# MCU_Power.net
KiCad netlist of a schematic drawn in Altium Designer
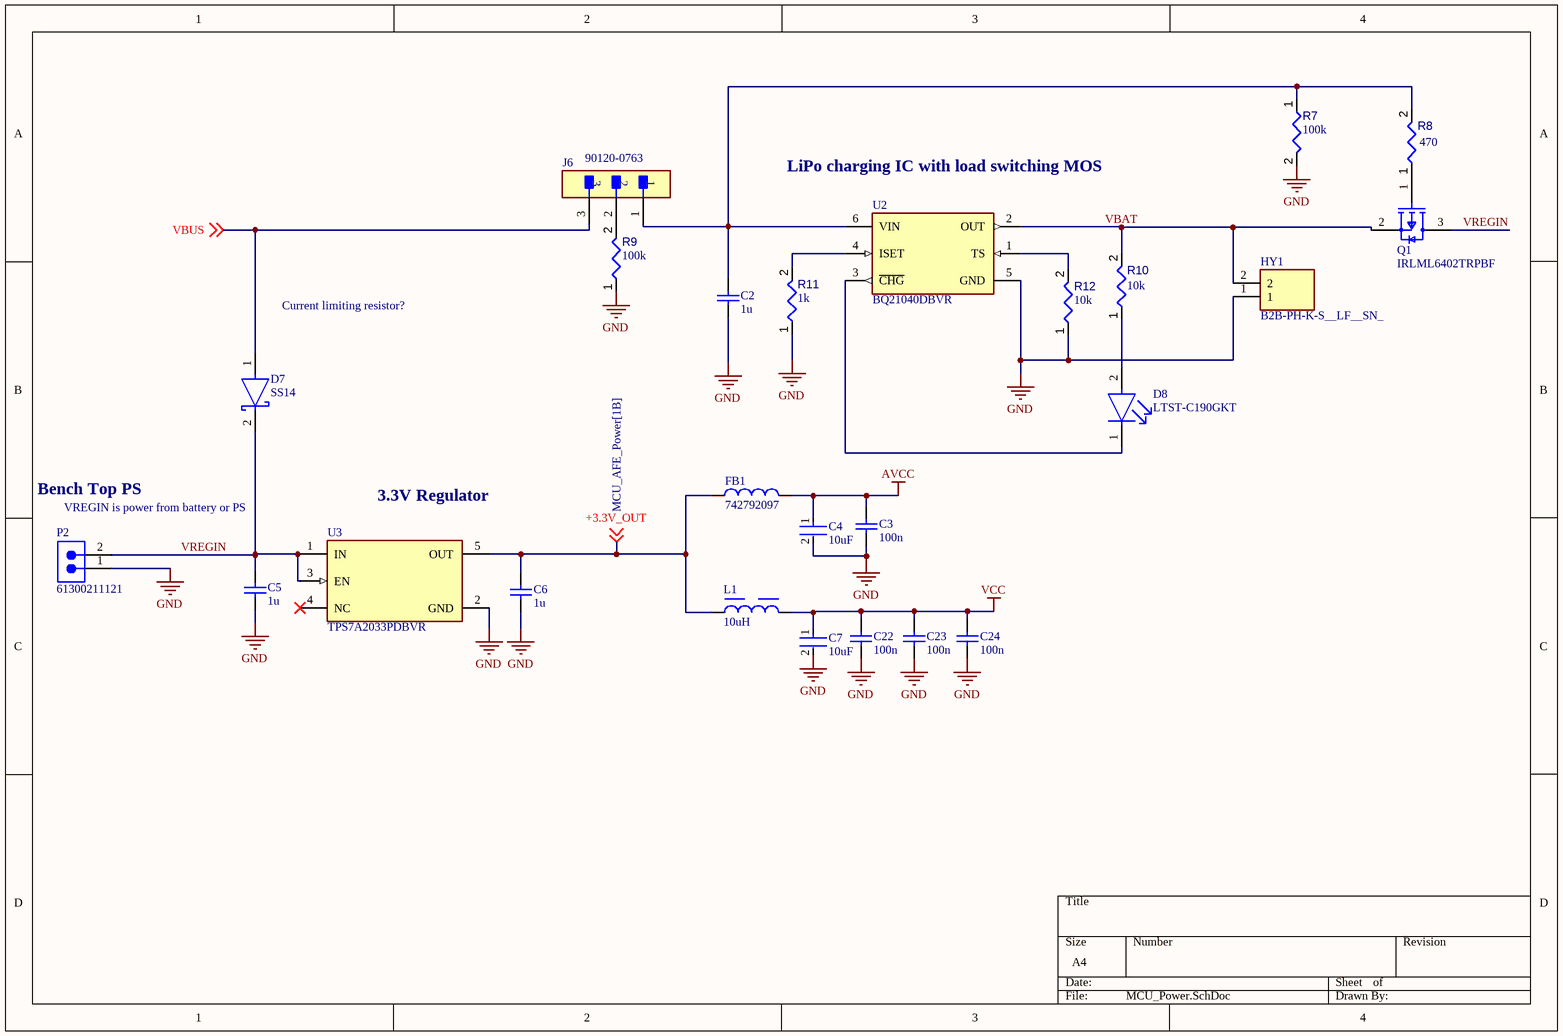
[diagram p0: MCU_Power.SchDoc]

(export (version "E")
  (design (tool "Eeschema 10.0.6"))
  (components
    (comp (ref "C2")
      (value "1u")
      (footprint "WCAP-CSGP_0402_L1W0.5H0.5")
      (description "CAP CER 10000PF 50V X7R 0402")
      (fields (field (name "TOLERANCE") "10%"))
      (libsource (lib "Altium Content Vault") (part "Capacitor_Non-Polarized"))
    )
    (comp (ref "C3")
      (value "100n")
      (footprint "WCAP-CSGP_0402_L1W0.5H0.5")
      (description "CAP CER 10000PF 50V X7R 0402")
      (fields (field (name "TOLERANCE") "10%"))
      (libsource (lib "Altium Content Vault") (part "Capacitor_Non-Polarized"))
    )
    (comp (ref "C4")
      (value "10uF")
      (footprint "FP-GRM188-0_1-e0_2_0_55-IPC_A")
      (description "Chip Multilayer Ceramic Capacitors for General Purpose, 0603, 10uF, X5R, 15%, 20%, 6.3V")
      (fields (field (name "VOLTAGE") "6.3V") (field (name "TOLERANCE") "20%"))
      (libsource (lib "Altium Content Vault") (part "02cd4be3c70576c341d710602a673aa"))
    )
    (comp (ref "C5")
      (value "1u")
      (footprint "WCAP-CSGP_0402_L1W0.5H0.5")
      (description "CAP CER 10000PF 50V X7R 0402")
      (fields (field (name "TOLERANCE") "10%"))
      (libsource (lib "Altium Content Vault") (part "Capacitor_Non-Polarized"))
    )
    (comp (ref "C6")
      (value "1u")
      (footprint "WCAP-CSGP_0402_L1W0.5H0.5")
      (description "CAP CER 10000PF 50V X7R 0402")
      (fields (field (name "TOLERANCE") "10%"))
      (libsource (lib "Altium Content Vault") (part "Capacitor_Non-Polarized"))
    )
    (comp (ref "C7")
      (value "10uF")
      (footprint "FP-GRM188-0_1-e0_2_0_55-IPC_A")
      (description "Chip Multilayer Ceramic Capacitors for General Purpose, 0603, 10uF, X5R, 15%, 20%, 6.3V")
      (fields (field (name "VOLTAGE") "6.3V") (field (name "TOLERANCE") "20%"))
      (libsource (lib "Altium Content Vault") (part "02cd4be3c70576c341d710602a673aa"))
    )
    (comp (ref "C22")
      (value "100n")
      (footprint "WCAP-CSGP_0402_L1W0.5H0.5")
      (description "CAP CER 10000PF 50V X7R 0402")
      (fields (field (name "TOLERANCE") "10%"))
      (libsource (lib "Altium Content Vault") (part "Capacitor_Non-Polarized"))
    )
    (comp (ref "C23")
      (value "100n")
      (footprint "WCAP-CSGP_0402_L1W0.5H0.5")
      (description "CAP CER 10000PF 50V X7R 0402")
      (fields (field (name "TOLERANCE") "10%"))
      (libsource (lib "Altium Content Vault") (part "Capacitor_Non-Polarized"))
    )
    (comp (ref "C24")
      (value "100n")
      (footprint "WCAP-CSGP_0402_L1W0.5H0.5")
      (description "CAP CER 10000PF 50V X7R 0402")
      (fields (field (name "TOLERANCE") "10%"))
      (libsource (lib "Altium Content Vault") (part "Capacitor_Non-Polarized"))
    )
    (comp (ref "D7")
      (value "SS14")
      (footprint "FP-403AE-MFG")
      (description "DIODE SCHOTTKY 40V 1A SMA")
      (fields
        (field (name "MANUFACTURER") "ON Semiconductor")
        (field (name "OCTOPART") "https://octopart.com/ss14-on+semiconductor-29205033")
      )
      (libsource (lib "Altium Content Vault") (part "360ad2f4ac25a952324d13796385471"))
    )
    (comp (ref "D8")
      (value "LTST-C190GKT")
      (footprint "FP-LTST-C190GKT-MFG")
      (description "LED GREEN CLEAR CHIP SMD")
      (fields (field (name "VOLTAGE") "2V"))
      (libsource (lib "Altium Content Vault") (part "8706943c75ba83719d021d2fdc84c58"))
    )
    (comp (ref "FB1")
      (value "742792097")
      (footprint "WE-CBF_0805_L2W1.2H0.9_HC")
      (fields (field (name "TOLERANCE") "25%"))
      (libsource (lib "Altium Content Vault") (part "Ferrite"))
    )
    (comp (ref "HY1")
      (value "B2B-PH-K-S__LF__SN_")
      (footprint "SamacSys:B2BPHKSLFSN")
      (description "Circulator or Directional Coupler")
      (fields (field (name "MANUFACTURER_PART_NUMBER") "B2B-PH-K-S (LF)(SN)"))
      (libsource (lib "*") (part "B2B-PH-K-S__LF__SN_"))
    )
    (comp (ref "J6")
      (value "90120-0763")
      (footprint "FP-90120-0763-MFG")
      (description "CONN HEADER VERT 3POS 2.54MM")
      (fields
        (field (name "MANUFACTURER") "Molex")
        (field (name "OCTOPART") "https://octopart.com/90120-0763-molex-655433")
      )
      (libsource (lib "Altium Content Vault") (part "0d3f023dd272f625e17a2be33dea85f"))
    )
    (comp (ref "L1")
      (value "10uH")
      (footprint "WE-LQS_2010")
      (description "74404020100 WE-LQS SMT Semi-Shielded Power Inductor")
      (libsource (lib "Altium Content Vault") (part "Inductor - 3"))
    )
    (comp (ref "P2")
      (value "61300211121")
      (footprint "61300211121")
      (libsource (lib "Altium Content Vault") (part "Header_Male_1R_02P"))
    )
    (comp (ref "Q1")
      (value "IRLML6402TRPBF")
      (footprint "FP-Micro3-MFG")
      (description "MOSFET P-CH 20V 3.7A SOT-23")
      (fields
        (field (name "OCTOPART") "https://octopart.com/irlml6402trpbf-infineon-65874989")
        (field (name "MANUFACTURER") "Infineon")
      )
      (libsource (lib "Altium Content Vault") (part "566027c8dc92b5207d53ac25ab3eb60"))
    )
    (comp (ref "R7")
      (value "100k")
      (footprint "RESC1005X40X25ML05T05")
      (description "Chip Resistor, 4.7 KOhm, +/- 1%, 63 mW, -55 to 155 degC, 0402 (1005 Metric)")
      (fields (field (name "TOLERANCE") "1%") (field (name "POWER") "63mW"))
      (libsource (lib "Christian Fenger") (part "RES-2"))
    )
    (comp (ref "R8")
      (value "470")
      (footprint "RESC1005X40X25ML05T05")
      (description "Chip Resistor, 4.7 KOhm, +/- 1%, 63 mW, -55 to 155 degC, 0402 (1005 Metric)")
      (fields (field (name "TOLERANCE") "1%") (field (name "POWER") "63mW"))
      (libsource (lib "Christian Fenger") (part "RES-2"))
    )
    (comp (ref "R9")
      (value "100k")
      (footprint "RESC1005X40X25ML05T05")
      (description "Chip Resistor, 4.7 KOhm, +/- 1%, 63 mW, -55 to 155 degC, 0402 (1005 Metric)")
      (fields (field (name "TOLERANCE") "1%") (field (name "POWER") "63mW"))
      (libsource (lib "Christian Fenger") (part "RES-2"))
    )
    (comp (ref "R10")
      (value "10k")
      (footprint "RESC1005X40X25ML05T05")
      (description "Chip Resistor, 4.7 KOhm, +/- 1%, 63 mW, -55 to 155 degC, 0402 (1005 Metric)")
      (fields (field (name "TOLERANCE") "1%") (field (name "POWER") "63mW"))
      (libsource (lib "Christian Fenger") (part "RES-2"))
    )
    (comp (ref "R11")
      (value "1k")
      (footprint "RESC1005X40X25ML05T05")
      (description "Chip Resistor, 4.7 KOhm, +/- 1%, 63 mW, -55 to 155 degC, 0402 (1005 Metric)")
      (fields (field (name "TOLERANCE") "1%") (field (name "POWER") "63mW"))
      (libsource (lib "Christian Fenger") (part "RES-2"))
    )
    (comp (ref "R12")
      (value "10k")
      (footprint "RESC1005X40X25ML05T05")
      (description "Chip Resistor, 4.7 KOhm, +/- 1%, 63 mW, -55 to 155 degC, 0402 (1005 Metric)")
      (fields (field (name "TOLERANCE") "1%") (field (name "POWER") "63mW"))
      (libsource (lib "Christian Fenger") (part "RES-2"))
    )
    (comp (ref "U2")
      (value "BQ21040DBVR")
      (footprint "FP-DBV0006A-MFG")
      (description "IC BATT CHG LI-ION 1CELL SOT23-6")
      (libsource (lib "Altium Content Vault") (part "3ee7d1eb50ab2d5c398f7a34a251785"))
    )
    (comp (ref "U3")
      (value "TPS7A2033PDBVR")
      (footprint "FP-DBV0005A-MFG")
      (description "IC REG LINEAR 3.3V 300MA SOT23-5")
      (libsource (lib "Altium Content Vault") (part "76aa7ad0ceb1012e0d85aeafc53095f"))
    )
  )
  (nets
    (net (code "1") (name "+3.3V_OUT") (class "Default")
      (node (ref "C6") (pin "2") (pinfunction "2_2") (pintype "passive"))
      (node (ref "FB1") (pin "1") (pinfunction "1_1") (pintype "passive"))
      (node (ref "L1") (pin "1") (pinfunction "1_1") (pintype "passive"))
      (node (ref "U3") (pin "5") (pinfunction "OUT_5") (pintype "passive"))
    )
    (net (code "2") (name "/VBAT") (class "Default")
      (node (ref "HY1") (pin "2") (pinfunction "2_2") (pintype "passive"))
      (node (ref "Q1") (pin "2") (pinfunction "S_2") (pintype "passive"))
      (node (ref "R10") (pin "2") (pinfunction "2_2") (pintype "passive"))
      (node (ref "U2") (pin "2") (pinfunction "OUT_2") (pintype "output"))
    )
    (net (code "3") (name "/VREGIN") (class "Default")
      (node (ref "C5") (pin "2") (pinfunction "2_2") (pintype "passive"))
      (node (ref "D7") (pin "2") (pinfunction "C_2") (pintype "passive"))
      (node (ref "P2") (pin "2") (pinfunction "2_2") (pintype "passive"))
      (node (ref "Q1") (pin "3") (pinfunction "D_3") (pintype "passive"))
      (node (ref "U3") (pin "1") (pinfunction "IN_1") (pintype "power_in"))
      (node (ref "U3") (pin "3") (pinfunction "EN_3") (pintype "input"))
    )
    (net (code "4") (name "AVCC") (class "Default")
      (node (ref "C3") (pin "2") (pinfunction "2_2") (pintype "passive"))
      (node (ref "C4") (pin "1") (pinfunction "1_1") (pintype "passive"))
      (node (ref "FB1") (pin "2") (pinfunction "2_2") (pintype "passive"))
    )
    (net (code "5") (name "GND") (class "Default")
      (node (ref "C2") (pin "1") (pinfunction "1_1") (pintype "passive"))
      (node (ref "C22") (pin "1") (pinfunction "1_1") (pintype "passive"))
      (node (ref "C23") (pin "1") (pinfunction "1_1") (pintype "passive"))
      (node (ref "C24") (pin "1") (pinfunction "1_1") (pintype "passive"))
      (node (ref "C3") (pin "1") (pinfunction "1_1") (pintype "passive"))
      (node (ref "C4") (pin "2") (pinfunction "2_2") (pintype "passive"))
      (node (ref "C5") (pin "1") (pinfunction "1_1") (pintype "passive"))
      (node (ref "C6") (pin "1") (pinfunction "1_1") (pintype "passive"))
      (node (ref "C7") (pin "2") (pinfunction "2_2") (pintype "passive"))
      (node (ref "HY1") (pin "1") (pinfunction "1_1") (pintype "passive"))
      (node (ref "P2") (pin "1") (pinfunction "1_1") (pintype "passive"))
      (node (ref "R11") (pin "1") (pinfunction "1_1") (pintype "passive"))
      (node (ref "R12") (pin "1") (pinfunction "1_1") (pintype "passive"))
      (node (ref "R7") (pin "2") (pinfunction "2_2") (pintype "passive"))
      (node (ref "R9") (pin "1") (pinfunction "1_1") (pintype "passive"))
      (node (ref "U2") (pin "5") (pinfunction "GND_5") (pintype "power_in"))
      (node (ref "U3") (pin "2") (pinfunction "GND_2") (pintype "power_in"))
    )
    (net (code "6") (name "Net-(D8-A)") (class "Default")
      (node (ref "D8") (pin "2") (pinfunction "A_2") (pintype "passive"))
      (node (ref "R10") (pin "1") (pinfunction "1_1") (pintype "passive"))
    )
    (net (code "7") (name "Net-(D8-C)") (class "Default")
      (node (ref "D8") (pin "1") (pinfunction "C_1") (pintype "passive"))
      (node (ref "U2") (pin "3") (pinfunction "~{CHG}_3") (pintype "output"))
    )
    (net (code "8") (name "Net-(J6-Pad2)") (class "Default")
      (node (ref "J6") (pin "2") (pinfunction "2_2") (pintype "passive"))
      (node (ref "R9") (pin "2") (pinfunction "2_2") (pintype "passive"))
    )
    (net (code "9") (name "Net-(Q1-G)") (class "Default")
      (node (ref "Q1") (pin "1") (pinfunction "G_1") (pintype "passive"))
      (node (ref "R8") (pin "1") (pinfunction "1_1") (pintype "passive"))
    )
    (net (code "10") (name "Net-(U2-ISET)") (class "Default")
      (node (ref "R11") (pin "2") (pinfunction "2_2") (pintype "passive"))
      (node (ref "U2") (pin "4") (pinfunction "ISET_4") (pintype "input"))
    )
    (net (code "11") (name "Net-(U2-TS)") (class "Default")
      (node (ref "R12") (pin "2") (pinfunction "2_2") (pintype "passive"))
      (node (ref "U2") (pin "1") (pinfunction "TS_1") (pintype "input"))
    )
    (net (code "12") (name "Net-(U2-VIN)") (class "Default")
      (node (ref "C2") (pin "2") (pinfunction "2_2") (pintype "passive"))
      (node (ref "J6") (pin "1") (pinfunction "1_1") (pintype "passive"))
      (node (ref "R7") (pin "1") (pinfunction "1_1") (pintype "passive"))
      (node (ref "R8") (pin "2") (pinfunction "2_2") (pintype "passive"))
      (node (ref "U2") (pin "6") (pinfunction "VIN_6") (pintype "power_in"))
    )
    (net (code "13") (name "VBUS") (class "Default")
      (node (ref "D7") (pin "1") (pinfunction "A_1") (pintype "passive"))
      (node (ref "J6") (pin "3") (pinfunction "3_3") (pintype "passive"))
    )
    (net (code "14") (name "VCC") (class "Default")
      (node (ref "C22") (pin "2") (pinfunction "2_2") (pintype "passive"))
      (node (ref "C23") (pin "2") (pinfunction "2_2") (pintype "passive"))
      (node (ref "C24") (pin "2") (pinfunction "2_2") (pintype "passive"))
      (node (ref "C7") (pin "1") (pinfunction "1_1") (pintype "passive"))
      (node (ref "L1") (pin "2") (pinfunction "2_2") (pintype "passive"))
    )
    (net (code "15") (name "unconnected-(U3-NC-Pad4)") (class "Default")
      (node (ref "U3") (pin "4") (pinfunction "NC_4") (pintype "passive+no_connect"))
    )
  )
)
